# blackfin_a_sdram.net
KiCad netlist of a schematic drawn in Altium Designer
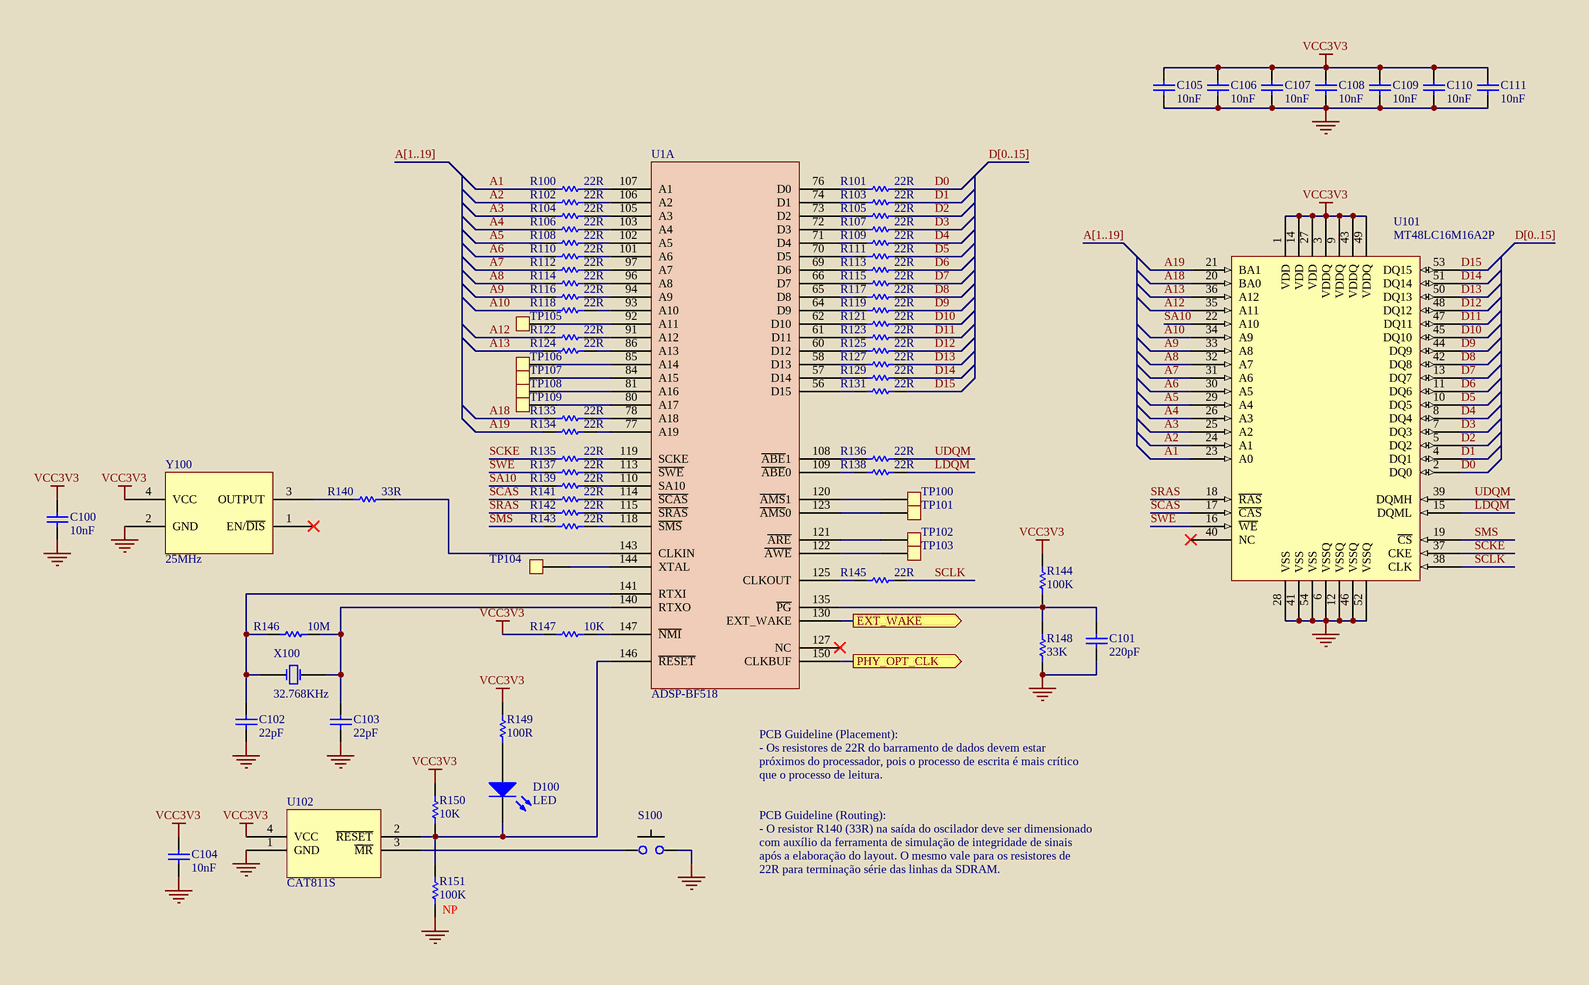
[diagram p0: blackfin_a_sdram.SchDoc]

(export (version "E")
  (design (tool "Eeschema 10.0.6"))
  (components
    (comp (ref "C100")
      (value "10nF")
      (footprint "blackfin_pcblib:C_0603")
      (fields
        (field (name "EVENDORPART#") "77-VJ0603Y103KXAPBC")
        (field (name "MANUFACTURER") "Vishay/Vitramon")
        (field (name "PART#") "VJ0603Y103KXAPW1BC")
      )
      (libsource (lib "blackfin_schlib") (part "Capacitor"))
    )
    (comp (ref "C101")
      (value "220pF")
      (footprint "blackfin_pcblib:C_0603")
      (fields
        (field (name "EVENDORPART#") "81-GRM18R72A221KA01D")
        (field (name "MANUFACTURER") "Murata")
        (field (name "PART#") "GRM188R72A221KA01D")
      )
      (libsource (lib "blackfin_schlib") (part "Capacitor"))
    )
    (comp (ref "C102")
      (value "22pF")
      (footprint "blackfin_pcblib:C_0603")
      (fields
        (field (name "EVENDORPART#") "581-06035A220J")
        (field (name "MANUFACTURER") "AVX")
        (field (name "PART#") "06035A220JAT2A")
      )
      (libsource (lib "blackfin_schlib") (part "Capacitor"))
    )
    (comp (ref "C103")
      (value "22pF")
      (footprint "blackfin_pcblib:C_0603")
      (fields
        (field (name "EVENDORPART#") "581-06035A220J")
        (field (name "MANUFACTURER") "AVX")
        (field (name "PART#") "06035A220JAT2A")
      )
      (libsource (lib "blackfin_schlib") (part "Capacitor"))
    )
    (comp (ref "C104")
      (value "10nF")
      (footprint "blackfin_pcblib:C_0603")
      (fields
        (field (name "EVENDORPART#") "77-VJ0603Y103KXAPBC")
        (field (name "MANUFACTURER") "Vishay/Vitramon")
        (field (name "PART#") "VJ0603Y103KXAPW1BC")
      )
      (libsource (lib "blackfin_schlib") (part "Capacitor"))
    )
    (comp (ref "C105")
      (value "10nF")
      (footprint "blackfin_pcblib:C_0603")
      (fields
        (field (name "EVENDORPART#") "77-VJ0603Y103KXAPBC")
        (field (name "MANUFACTURER") "Vishay/Vitramon")
        (field (name "PART#") "VJ0603Y103KXAPW1BC")
      )
      (libsource (lib "blackfin_schlib") (part "Capacitor"))
    )
    (comp (ref "C106")
      (value "10nF")
      (footprint "blackfin_pcblib:C_0603")
      (fields
        (field (name "EVENDORPART#") "77-VJ0603Y103KXAPBC")
        (field (name "MANUFACTURER") "Vishay/Vitramon")
        (field (name "PART#") "VJ0603Y103KXAPW1BC")
      )
      (libsource (lib "blackfin_schlib") (part "Capacitor"))
    )
    (comp (ref "C107")
      (value "10nF")
      (footprint "blackfin_pcblib:C_0603")
      (fields
        (field (name "EVENDORPART#") "77-VJ0603Y103KXAPBC")
        (field (name "MANUFACTURER") "Vishay/Vitramon")
        (field (name "PART#") "VJ0603Y103KXAPW1BC")
      )
      (libsource (lib "blackfin_schlib") (part "Capacitor"))
    )
    (comp (ref "C108")
      (value "10nF")
      (footprint "blackfin_pcblib:C_0603")
      (fields
        (field (name "EVENDORPART#") "77-VJ0603Y103KXAPBC")
        (field (name "MANUFACTURER") "Vishay/Vitramon")
        (field (name "PART#") "VJ0603Y103KXAPW1BC")
      )
      (libsource (lib "blackfin_schlib") (part "Capacitor"))
    )
    (comp (ref "C109")
      (value "10nF")
      (footprint "blackfin_pcblib:C_0603")
      (fields
        (field (name "EVENDORPART#") "77-VJ0603Y103KXAPBC")
        (field (name "MANUFACTURER") "Vishay/Vitramon")
        (field (name "PART#") "VJ0603Y103KXAPW1BC")
      )
      (libsource (lib "blackfin_schlib") (part "Capacitor"))
    )
    (comp (ref "C110")
      (value "10nF")
      (footprint "blackfin_pcblib:C_0603")
      (fields
        (field (name "EVENDORPART#") "77-VJ0603Y103KXAPBC")
        (field (name "MANUFACTURER") "Vishay/Vitramon")
        (field (name "PART#") "VJ0603Y103KXAPW1BC")
      )
      (libsource (lib "blackfin_schlib") (part "Capacitor"))
    )
    (comp (ref "C111")
      (value "10nF")
      (footprint "blackfin_pcblib:C_0603")
      (fields
        (field (name "EVENDORPART#") "77-VJ0603Y103KXAPBC")
        (field (name "MANUFACTURER") "Vishay/Vitramon")
        (field (name "PART#") "VJ0603Y103KXAPW1BC")
      )
      (libsource (lib "blackfin_schlib") (part "Capacitor"))
    )
    (comp (ref "D100")
      (value "LED")
      (footprint "blackfin_pcblib:LED_0603")
      (description "Red LED")
      (fields (field (name "EVENDORPART#") "638-QTLP600C2TR") (field (name "MANUFACTURER") "Everlight"))
      (libsource (lib "blackfin_schlib") (part "LED"))
    )
    (comp (ref "R100")
      (value "22R")
      (footprint "blackfin_pcblib:R_0402")
      (fields
        (field (name "EVENDORPART#") "71-CRCW0402J-22-E3")
        (field (name "PART#") "CRCW040222R0JNED")
        (field (name "MANUFACTURER") "Vishay/Dale")
      )
      (libsource (lib "blackfin_schlib") (part "Resistor"))
    )
    (comp (ref "R101")
      (value "22R")
      (footprint "blackfin_pcblib:R_0402")
      (fields
        (field (name "EVENDORPART#") "71-CRCW0402J-22-E3")
        (field (name "PART#") "CRCW040222R0JNED")
        (field (name "MANUFACTURER") "Vishay/Dale")
      )
      (libsource (lib "blackfin_schlib") (part "Resistor"))
    )
    (comp (ref "R102")
      (value "22R")
      (footprint "blackfin_pcblib:R_0402")
      (fields
        (field (name "EVENDORPART#") "71-CRCW0402J-22-E3")
        (field (name "PART#") "CRCW040222R0JNED")
        (field (name "MANUFACTURER") "Vishay/Dale")
      )
      (libsource (lib "blackfin_schlib") (part "Resistor"))
    )
    (comp (ref "R103")
      (value "22R")
      (footprint "blackfin_pcblib:R_0402")
      (fields
        (field (name "EVENDORPART#") "71-CRCW0402J-22-E3")
        (field (name "PART#") "CRCW040222R0JNED")
        (field (name "MANUFACTURER") "Vishay/Dale")
      )
      (libsource (lib "blackfin_schlib") (part "Resistor"))
    )
    (comp (ref "R104")
      (value "22R")
      (footprint "blackfin_pcblib:R_0402")
      (fields
        (field (name "EVENDORPART#") "71-CRCW0402J-22-E3")
        (field (name "PART#") "CRCW040222R0JNED")
        (field (name "MANUFACTURER") "Vishay/Dale")
      )
      (libsource (lib "blackfin_schlib") (part "Resistor"))
    )
    (comp (ref "R105")
      (value "22R")
      (footprint "blackfin_pcblib:R_0402")
      (fields
        (field (name "EVENDORPART#") "71-CRCW0402J-22-E3")
        (field (name "PART#") "CRCW040222R0JNED")
        (field (name "MANUFACTURER") "Vishay/Dale")
      )
      (libsource (lib "blackfin_schlib") (part "Resistor"))
    )
    (comp (ref "R106")
      (value "22R")
      (footprint "blackfin_pcblib:R_0402")
      (fields
        (field (name "EVENDORPART#") "71-CRCW0402J-22-E3")
        (field (name "PART#") "CRCW040222R0JNED")
        (field (name "MANUFACTURER") "Vishay/Dale")
      )
      (libsource (lib "blackfin_schlib") (part "Resistor"))
    )
    (comp (ref "R107")
      (value "22R")
      (footprint "blackfin_pcblib:R_0402")
      (fields
        (field (name "EVENDORPART#") "71-CRCW0402J-22-E3")
        (field (name "PART#") "CRCW040222R0JNED")
        (field (name "MANUFACTURER") "Vishay/Dale")
      )
      (libsource (lib "blackfin_schlib") (part "Resistor"))
    )
    (comp (ref "R108")
      (value "22R")
      (footprint "blackfin_pcblib:R_0402")
      (fields
        (field (name "EVENDORPART#") "71-CRCW0402J-22-E3")
        (field (name "PART#") "CRCW040222R0JNED")
        (field (name "MANUFACTURER") "Vishay/Dale")
      )
      (libsource (lib "blackfin_schlib") (part "Resistor"))
    )
    (comp (ref "R109")
      (value "22R")
      (footprint "blackfin_pcblib:R_0402")
      (fields
        (field (name "EVENDORPART#") "71-CRCW0402J-22-E3")
        (field (name "PART#") "CRCW040222R0JNED")
        (field (name "MANUFACTURER") "Vishay/Dale")
      )
      (libsource (lib "blackfin_schlib") (part "Resistor"))
    )
    (comp (ref "R110")
      (value "22R")
      (footprint "blackfin_pcblib:R_0402")
      (fields
        (field (name "EVENDORPART#") "71-CRCW0402J-22-E3")
        (field (name "PART#") "CRCW040222R0JNED")
        (field (name "MANUFACTURER") "Vishay/Dale")
      )
      (libsource (lib "blackfin_schlib") (part "Resistor"))
    )
    (comp (ref "R111")
      (value "22R")
      (footprint "blackfin_pcblib:R_0402")
      (fields
        (field (name "EVENDORPART#") "71-CRCW0402J-22-E3")
        (field (name "PART#") "CRCW040222R0JNED")
        (field (name "MANUFACTURER") "Vishay/Dale")
      )
      (libsource (lib "blackfin_schlib") (part "Resistor"))
    )
    (comp (ref "R112")
      (value "22R")
      (footprint "blackfin_pcblib:R_0402")
      (fields
        (field (name "EVENDORPART#") "71-CRCW0402J-22-E3")
        (field (name "PART#") "CRCW040222R0JNED")
        (field (name "MANUFACTURER") "Vishay/Dale")
      )
      (libsource (lib "blackfin_schlib") (part "Resistor"))
    )
    (comp (ref "R113")
      (value "22R")
      (footprint "blackfin_pcblib:R_0402")
      (fields
        (field (name "EVENDORPART#") "71-CRCW0402J-22-E3")
        (field (name "PART#") "CRCW040222R0JNED")
        (field (name "MANUFACTURER") "Vishay/Dale")
      )
      (libsource (lib "blackfin_schlib") (part "Resistor"))
    )
    (comp (ref "R114")
      (value "22R")
      (footprint "blackfin_pcblib:R_0402")
      (fields
        (field (name "EVENDORPART#") "71-CRCW0402J-22-E3")
        (field (name "PART#") "CRCW040222R0JNED")
        (field (name "MANUFACTURER") "Vishay/Dale")
      )
      (libsource (lib "blackfin_schlib") (part "Resistor"))
    )
    (comp (ref "R115")
      (value "22R")
      (footprint "blackfin_pcblib:R_0402")
      (fields
        (field (name "EVENDORPART#") "71-CRCW0402J-22-E3")
        (field (name "PART#") "CRCW040222R0JNED")
        (field (name "MANUFACTURER") "Vishay/Dale")
      )
      (libsource (lib "blackfin_schlib") (part "Resistor"))
    )
    (comp (ref "R116")
      (value "22R")
      (footprint "blackfin_pcblib:R_0402")
      (fields
        (field (name "EVENDORPART#") "71-CRCW0402J-22-E3")
        (field (name "PART#") "CRCW040222R0JNED")
        (field (name "MANUFACTURER") "Vishay/Dale")
      )
      (libsource (lib "blackfin_schlib") (part "Resistor"))
    )
    (comp (ref "R117")
      (value "22R")
      (footprint "blackfin_pcblib:R_0402")
      (fields
        (field (name "EVENDORPART#") "71-CRCW0402J-22-E3")
        (field (name "PART#") "CRCW040222R0JNED")
        (field (name "MANUFACTURER") "Vishay/Dale")
      )
      (libsource (lib "blackfin_schlib") (part "Resistor"))
    )
    (comp (ref "R118")
      (value "22R")
      (footprint "blackfin_pcblib:R_0402")
      (fields
        (field (name "EVENDORPART#") "71-CRCW0402J-22-E3")
        (field (name "PART#") "CRCW040222R0JNED")
        (field (name "MANUFACTURER") "Vishay/Dale")
      )
      (libsource (lib "blackfin_schlib") (part "Resistor"))
    )
    (comp (ref "R119")
      (value "22R")
      (footprint "blackfin_pcblib:R_0402")
      (fields
        (field (name "EVENDORPART#") "71-CRCW0402J-22-E3")
        (field (name "PART#") "CRCW040222R0JNED")
        (field (name "MANUFACTURER") "Vishay/Dale")
      )
      (libsource (lib "blackfin_schlib") (part "Resistor"))
    )
    (comp (ref "R121")
      (value "22R")
      (footprint "blackfin_pcblib:R_0402")
      (fields
        (field (name "EVENDORPART#") "71-CRCW0402J-22-E3")
        (field (name "PART#") "CRCW040222R0JNED")
        (field (name "MANUFACTURER") "Vishay/Dale")
      )
      (libsource (lib "blackfin_schlib") (part "Resistor"))
    )
    (comp (ref "R122")
      (value "22R")
      (footprint "blackfin_pcblib:R_0402")
      (fields
        (field (name "EVENDORPART#") "71-CRCW0402J-22-E3")
        (field (name "PART#") "CRCW040222R0JNED")
        (field (name "MANUFACTURER") "Vishay/Dale")
      )
      (libsource (lib "blackfin_schlib") (part "Resistor"))
    )
    (comp (ref "R123")
      (value "22R")
      (footprint "blackfin_pcblib:R_0402")
      (fields
        (field (name "EVENDORPART#") "71-CRCW0402J-22-E3")
        (field (name "PART#") "CRCW040222R0JNED")
        (field (name "MANUFACTURER") "Vishay/Dale")
      )
      (libsource (lib "blackfin_schlib") (part "Resistor"))
    )
    (comp (ref "R124")
      (value "22R")
      (footprint "blackfin_pcblib:R_0402")
      (fields
        (field (name "EVENDORPART#") "71-CRCW0402J-22-E3")
        (field (name "PART#") "CRCW040222R0JNED")
        (field (name "MANUFACTURER") "Vishay/Dale")
      )
      (libsource (lib "blackfin_schlib") (part "Resistor"))
    )
    (comp (ref "R125")
      (value "22R")
      (footprint "blackfin_pcblib:R_0402")
      (fields
        (field (name "EVENDORPART#") "71-CRCW0402J-22-E3")
        (field (name "PART#") "CRCW040222R0JNED")
        (field (name "MANUFACTURER") "Vishay/Dale")
      )
      (libsource (lib "blackfin_schlib") (part "Resistor"))
    )
    (comp (ref "R127")
      (value "22R")
      (footprint "blackfin_pcblib:R_0402")
      (fields
        (field (name "EVENDORPART#") "71-CRCW0402J-22-E3")
        (field (name "PART#") "CRCW040222R0JNED")
        (field (name "MANUFACTURER") "Vishay/Dale")
      )
      (libsource (lib "blackfin_schlib") (part "Resistor"))
    )
    (comp (ref "R129")
      (value "22R")
      (footprint "blackfin_pcblib:R_0402")
      (fields
        (field (name "EVENDORPART#") "71-CRCW0402J-22-E3")
        (field (name "PART#") "CRCW040222R0JNED")
        (field (name "MANUFACTURER") "Vishay/Dale")
      )
      (libsource (lib "blackfin_schlib") (part "Resistor"))
    )
    (comp (ref "R131")
      (value "22R")
      (footprint "blackfin_pcblib:R_0402")
      (fields
        (field (name "EVENDORPART#") "71-CRCW0402J-22-E3")
        (field (name "PART#") "CRCW040222R0JNED")
        (field (name "MANUFACTURER") "Vishay/Dale")
      )
      (libsource (lib "blackfin_schlib") (part "Resistor"))
    )
    (comp (ref "R133")
      (value "22R")
      (footprint "blackfin_pcblib:R_0402")
      (fields
        (field (name "EVENDORPART#") "71-CRCW0402J-22-E3")
        (field (name "PART#") "CRCW040222R0JNED")
        (field (name "MANUFACTURER") "Vishay/Dale")
      )
      (libsource (lib "blackfin_schlib") (part "Resistor"))
    )
    (comp (ref "R134")
      (value "22R")
      (footprint "blackfin_pcblib:R_0402")
      (fields
        (field (name "EVENDORPART#") "71-CRCW0402J-22-E3")
        (field (name "PART#") "CRCW040222R0JNED")
        (field (name "MANUFACTURER") "Vishay/Dale")
      )
      (libsource (lib "blackfin_schlib") (part "Resistor"))
    )
    (comp (ref "R135")
      (value "22R")
      (footprint "blackfin_pcblib:R_0402")
      (fields
        (field (name "EVENDORPART#") "71-CRCW0402J-22-E3")
        (field (name "PART#") "CRCW040222R0JNED")
        (field (name "MANUFACTURER") "Vishay/Dale")
      )
      (libsource (lib "blackfin_schlib") (part "Resistor"))
    )
    (comp (ref "R136")
      (value "22R")
      (footprint "blackfin_pcblib:R_0402")
      (fields
        (field (name "EVENDORPART#") "71-CRCW0402J-22-E3")
        (field (name "PART#") "CRCW040222R0JNED")
        (field (name "MANUFACTURER") "Vishay/Dale")
      )
      (libsource (lib "blackfin_schlib") (part "Resistor"))
    )
    (comp (ref "R137")
      (value "22R")
      (footprint "blackfin_pcblib:R_0402")
      (fields
        (field (name "EVENDORPART#") "71-CRCW0402J-22-E3")
        (field (name "PART#") "CRCW040222R0JNED")
        (field (name "MANUFACTURER") "Vishay/Dale")
      )
      (libsource (lib "blackfin_schlib") (part "Resistor"))
    )
    (comp (ref "R138")
      (value "22R")
      (footprint "blackfin_pcblib:R_0402")
      (fields
        (field (name "EVENDORPART#") "71-CRCW0402J-22-E3")
        (field (name "PART#") "CRCW040222R0JNED")
        (field (name "MANUFACTURER") "Vishay/Dale")
      )
      (libsource (lib "blackfin_schlib") (part "Resistor"))
    )
    (comp (ref "R139")
      (value "22R")
      (footprint "blackfin_pcblib:R_0402")
      (fields
        (field (name "EVENDORPART#") "71-CRCW0402J-22-E3")
        (field (name "PART#") "CRCW040222R0JNED")
        (field (name "MANUFACTURER") "Vishay/Dale")
      )
      (libsource (lib "blackfin_schlib") (part "Resistor"))
    )
    (comp (ref "R140")
      (value "33R")
      (footprint "blackfin_pcblib:R_0402")
      (fields
        (field (name "EVENDORPART#") "71-CRCW0402J-33-E3")
        (field (name "PART#") "CRCW040233R0JNED")
        (field (name "MANUFACTURER") "Vishay/Dale")
      )
      (libsource (lib "blackfin_schlib") (part "Resistor"))
    )
    (comp (ref "R141")
      (value "22R")
      (footprint "blackfin_pcblib:R_0402")
      (fields
        (field (name "EVENDORPART#") "71-CRCW0402J-22-E3")
        (field (name "PART#") "CRCW040222R0JNED")
        (field (name "MANUFACTURER") "Vishay/Dale")
      )
      (libsource (lib "blackfin_schlib") (part "Resistor"))
    )
    (comp (ref "R142")
      (value "22R")
      (footprint "blackfin_pcblib:R_0402")
      (fields
        (field (name "EVENDORPART#") "71-CRCW0402J-22-E3")
        (field (name "PART#") "CRCW040222R0JNED")
        (field (name "MANUFACTURER") "Vishay/Dale")
      )
      (libsource (lib "blackfin_schlib") (part "Resistor"))
    )
    (comp (ref "R143")
      (value "22R")
      (footprint "blackfin_pcblib:R_0402")
      (fields
        (field (name "EVENDORPART#") "71-CRCW0402J-22-E3")
        (field (name "PART#") "CRCW040222R0JNED")
        (field (name "MANUFACTURER") "Vishay/Dale")
      )
      (libsource (lib "blackfin_schlib") (part "Resistor"))
    )
    (comp (ref "R144")
      (value "100K")
      (footprint "blackfin_pcblib:R_0603")
      (fields
        (field (name "EVENDORPART#") "71-CRCW0603J-100K-E3")
        (field (name "PART#") "CRCW0603100KJNEA")
        (field (name "MANUFACTURER") "Vishay/Dale")
      )
      (libsource (lib "blackfin_schlib") (part "Resistor"))
    )
    (comp (ref "R145")
      (value "22R")
      (footprint "blackfin_pcblib:R_0402")
      (fields
        (field (name "EVENDORPART#") "71-CRCW0402J-22-E3")
        (field (name "PART#") "CRCW040222R0JNED")
        (field (name "MANUFACTURER") "Vishay/Dale")
      )
      (libsource (lib "blackfin_schlib") (part "Resistor"))
    )
    (comp (ref "R146")
      (value "10M")
      (footprint "blackfin_pcblib:R_0603")
      (fields
        (field (name "EVENDORPART#") "652-CR0603FX-1005ELF")
        (field (name "PART#") "CR0603-FX-1005ELF")
        (field (name "MANUFACTURER") "Bourns")
      )
      (libsource (lib "blackfin_schlib") (part "Resistor"))
    )
    (comp (ref "R147")
      (value "10K")
      (footprint "blackfin_pcblib:R_0603")
      (fields
        (field (name "EVENDORPART#") "71-CRCW0603-10K-E3")
        (field (name "PART#") "CRCW060310K0FKEA")
        (field (name "MANUFACTURER") "Vishay/Dale")
      )
      (libsource (lib "blackfin_schlib") (part "Resistor"))
    )
    (comp (ref "R148")
      (value "33K")
      (footprint "blackfin_pcblib:R_0603")
      (fields
        (field (name "EVENDORPART#") "71-CRCW0603J-33K-E3")
        (field (name "PART#") "CRCW060333K0JNEA")
        (field (name "MANUFACTURER") "Vishay/Dale")
      )
      (libsource (lib "blackfin_schlib") (part "Resistor"))
    )
    (comp (ref "R149")
      (value "100R")
      (footprint "blackfin_pcblib:R_0603")
      (fields
        (field (name "EVENDORPART#") "71-CRCW0603-100-E3")
        (field (name "PART#") "CRCW0603100RFKEA")
        (field (name "MANUFACTURER") "Vishay/Dale")
      )
      (libsource (lib "blackfin_schlib") (part "Resistor"))
    )
    (comp (ref "R150")
      (value "10K")
      (footprint "blackfin_pcblib:R_0603")
      (fields
        (field (name "EVENDORPART#") "71-CRCW0603-10K-E3")
        (field (name "PART#") "CRCW060310K0FKEA")
        (field (name "MANUFACTURER") "Vishay/Dale")
      )
      (libsource (lib "blackfin_schlib") (part "Resistor"))
    )
    (comp (ref "R151")
      (value "100K")
      (footprint "blackfin_pcblib:R_0603")
      (fields
        (field (name "EVENDORPART#") "71-CRCW0603J-100K-E3")
        (field (name "PART#") "CRCW0603100KJNEA")
        (field (name "MANUFACTURER") "Vishay/Dale")
      )
      (libsource (lib "blackfin_schlib") (part "Resistor"))
    )
    (comp (ref "S100")
      (value "Push Button")
      (footprint "blackfin_pcblib:Push Button")
      (fields
        (field (name "EVENDORPART#") "611-PTS645SH50SMTRLF")
        (field (name "PART#") "PTS645SH50SMTRLFS")
        (field (name "MANUFACTURER") "C&K Components")
      )
      (libsource (lib "*") (part "Push Button"))
    )
    (comp (ref "TP100")
      (value "Test Point")
      (footprint "blackfin_pcblib:Test Point")
      (fields (field (name "EVENDORPART#") "NÃO SE APLICA"))
      (libsource (lib "blackfin_schlib") (part "Test Point"))
    )
    (comp (ref "TP101")
      (value "Test Point")
      (footprint "blackfin_pcblib:Test Point")
      (fields (field (name "EVENDORPART#") "NÃO SE APLICA"))
      (libsource (lib "blackfin_schlib") (part "Test Point"))
    )
    (comp (ref "TP102")
      (value "Test Point")
      (footprint "blackfin_pcblib:Test Point")
      (fields (field (name "EVENDORPART#") "NÃO SE APLICA"))
      (libsource (lib "blackfin_schlib") (part "Test Point"))
    )
    (comp (ref "TP103")
      (value "Test Point")
      (footprint "blackfin_pcblib:Test Point")
      (fields (field (name "EVENDORPART#") "NÃO SE APLICA"))
      (libsource (lib "blackfin_schlib") (part "Test Point"))
    )
    (comp (ref "TP104")
      (value "Test Point")
      (footprint "blackfin_pcblib:Test Point")
      (fields (field (name "EVENDORPART#") "NÃO SE APLICA"))
      (libsource (lib "") (part "Test Point_1"))
    )
    (comp (ref "TP105")
      (value "Test Point")
      (footprint "blackfin_pcblib:Test Point")
      (fields (field (name "EVENDORPART#") "NÃO SE APLICA"))
      (libsource (lib "") (part "Test Point_1"))
    )
    (comp (ref "TP106")
      (value "Test Point")
      (footprint "blackfin_pcblib:Test Point")
      (fields (field (name "EVENDORPART#") "NÃO SE APLICA"))
      (libsource (lib "") (part "Test Point_1"))
    )
    (comp (ref "TP107")
      (value "Test Point")
      (footprint "blackfin_pcblib:Test Point")
      (fields (field (name "EVENDORPART#") "NÃO SE APLICA"))
      (libsource (lib "") (part "Test Point_1"))
    )
    (comp (ref "TP108")
      (value "Test Point")
      (footprint "blackfin_pcblib:Test Point")
      (fields (field (name "EVENDORPART#") "NÃO SE APLICA"))
      (libsource (lib "") (part "Test Point_1"))
    )
    (comp (ref "TP109")
      (value "Test Point")
      (footprint "blackfin_pcblib:Test Point")
      (fields (field (name "EVENDORPART#") "NÃO SE APLICA"))
      (libsource (lib "") (part "Test Point_1"))
    )
    (comp (ref "U1")
      (value "ADSP-BF518")
      (footprint "blackfin_pcblib:LQFP-176")
      (fields (field (name "EVENDORPART#") "ADSP-BF518BSWZ-4") (field (name "MANUFACTURER") "Analog Devices"))
      (libsource (lib "blackfin_schlib") (part "ADSP-BF518"))
    )
    (comp (ref "U101")
      (value "MT48LC16M16A2P")
      (footprint "blackfin_pcblib:TSOP-54")
      (fields
        (field (name "PART#") "MT48LC16M16A2P-75:D TR")
        (field (name "EVENDORPART#") "557-1059-1-ND")
        (field (name "MANUFACTURER") "Micron")
      )
      (libsource (lib "blackfin_schlib") (part "MT48LC16M16A2P"))
    )
    (comp (ref "U102")
      (value "CAT811S")
      (footprint "blackfin_pcblib:SOT-143")
      (fields
        (field (name "PART#") "CAT811STBI-GT3")
        (field (name "MANUFACTURER") "ON Semiconductor")
        (field (name "EVENDORPART#") "698-CAT811STBI-GT3")
      )
      (libsource (lib "*") (part "CAT811S"))
    )
    (comp (ref "X100")
      (value "32.768KHz")
      (footprint "blackfin_pcblib:XTAL_32.768kHz")
      (fields
        (field (name "EVENDORPART#") "SER2405CT-ND")
        (field (name "PART#") "MC-405")
        (field (name "MANUFACTURER") "Epson")
      )
      (libsource (lib "blackfin_schlib") (part "XTAL"))
    )
    (comp (ref "Y100")
      (value "25MHz")
      (footprint "blackfin_pcblib:OSC_25MHz")
      (fields
        (field (name "EVENDORPART#") "815-ASV-25-EJ-T")
        (field (name "PART#") "ASV-25.000MHZ-EJ-T")
        (field (name "MANUFACTURER") "ABRACON")
      )
      (libsource (lib "blackfin_schlib") (part "Oscillator_25MHz"))
    )
  )
  (nets
    (net (code "6") (name "/A1") (class "Default")
      (node (ref "R100") (pin "1") (pinfunction "1_1") (pintype "passive"))
      (node (ref "U101") (pin "23") (pinfunction "A0_23") (pintype "input"))
    )
    (net (code "7") (name "/A2") (class "Default")
      (node (ref "R102") (pin "1") (pinfunction "1_1") (pintype "passive"))
      (node (ref "U101") (pin "24") (pinfunction "A1_24") (pintype "input"))
    )
    (net (code "8") (name "/A3") (class "Default")
      (node (ref "R104") (pin "1") (pinfunction "1_1") (pintype "passive"))
      (node (ref "U101") (pin "25") (pinfunction "A2_25") (pintype "input"))
    )
    (net (code "9") (name "/A4") (class "Default")
      (node (ref "R106") (pin "1") (pinfunction "1_1") (pintype "passive"))
      (node (ref "U101") (pin "26") (pinfunction "A3_26") (pintype "input"))
    )
    (net (code "10") (name "/A5") (class "Default")
      (node (ref "R108") (pin "1") (pinfunction "1_1") (pintype "passive"))
      (node (ref "U101") (pin "29") (pinfunction "A4_29") (pintype "input"))
    )
    (net (code "11") (name "/A6") (class "Default")
      (node (ref "R110") (pin "1") (pinfunction "1_1") (pintype "passive"))
      (node (ref "U101") (pin "30") (pinfunction "A5_30") (pintype "input"))
    )
    (net (code "12") (name "/A7") (class "Default")
      (node (ref "R112") (pin "1") (pinfunction "1_1") (pintype "passive"))
      (node (ref "U101") (pin "31") (pinfunction "A6_31") (pintype "input"))
    )
    (net (code "13") (name "/A8") (class "Default")
      (node (ref "R114") (pin "1") (pinfunction "1_1") (pintype "passive"))
      (node (ref "U101") (pin "32") (pinfunction "A7_32") (pintype "input"))
    )
    (net (code "14") (name "/A9") (class "Default")
      (node (ref "R116") (pin "1") (pinfunction "1_1") (pintype "passive"))
      (node (ref "U101") (pin "33") (pinfunction "A8_33") (pintype "input"))
    )
    (net (code "15") (name "/A10") (class "Default")
      (node (ref "R118") (pin "1") (pinfunction "1_1") (pintype "passive"))
      (node (ref "U101") (pin "34") (pinfunction "A9_34") (pintype "input"))
    )
    (net (code "16") (name "/A12") (class "Default")
      (node (ref "R122") (pin "1") (pinfunction "1_1") (pintype "passive"))
      (node (ref "U101") (pin "35") (pinfunction "A11_35") (pintype "input"))
    )
    (net (code "17") (name "/A13") (class "Default")
      (node (ref "R124") (pin "1") (pinfunction "1_1") (pintype "passive"))
      (node (ref "U101") (pin "36") (pinfunction "A12_36") (pintype "input"))
    )
    (net (code "18") (name "/A18") (class "Default")
      (node (ref "R133") (pin "1") (pinfunction "1_1") (pintype "passive"))
      (node (ref "U101") (pin "20") (pinfunction "BA0_20") (pintype "input"))
    )
    (net (code "19") (name "/A19") (class "Default")
      (node (ref "R134") (pin "1") (pinfunction "1_1") (pintype "passive"))
      (node (ref "U101") (pin "21") (pinfunction "BA1_21") (pintype "input"))
    )
    (net (code "21") (name "/D0") (class "Default")
      (node (ref "R101") (pin "2") (pinfunction "2_2") (pintype "passive"))
      (node (ref "U101") (pin "2") (pinfunction "DQ0_2") (pintype "bidirectional"))
    )
    (net (code "22") (name "/D1") (class "Default")
      (node (ref "R103") (pin "2") (pinfunction "2_2") (pintype "passive"))
      (node (ref "U101") (pin "4") (pinfunction "DQ1_4") (pintype "bidirectional"))
    )
    (net (code "23") (name "/D2") (class "Default")
      (node (ref "R105") (pin "2") (pinfunction "2_2") (pintype "passive"))
      (node (ref "U101") (pin "5") (pinfunction "DQ2_5") (pintype "bidirectional"))
    )
    (net (code "24") (name "/D3") (class "Default")
      (node (ref "R107") (pin "2") (pinfunction "2_2") (pintype "passive"))
      (node (ref "U101") (pin "7") (pinfunction "DQ3_7") (pintype "bidirectional"))
    )
    (net (code "25") (name "/D4") (class "Default")
      (node (ref "R109") (pin "2") (pinfunction "2_2") (pintype "passive"))
      (node (ref "U101") (pin "8") (pinfunction "DQ4_8") (pintype "bidirectional"))
    )
    (net (code "26") (name "/D5") (class "Default")
      (node (ref "R111") (pin "2") (pinfunction "2_2") (pintype "passive"))
      (node (ref "U101") (pin "10") (pinfunction "DQ5_10") (pintype "bidirectional"))
    )
    (net (code "27") (name "/D6") (class "Default")
      (node (ref "R113") (pin "2") (pinfunction "2_2") (pintype "passive"))
      (node (ref "U101") (pin "11") (pinfunction "DQ6_11") (pintype "bidirectional"))
    )
    (net (code "28") (name "/D7") (class "Default")
      (node (ref "R115") (pin "2") (pinfunction "2_2") (pintype "passive"))
      (node (ref "U101") (pin "13") (pinfunction "DQ7_13") (pintype "bidirectional"))
    )
    (net (code "29") (name "/D8") (class "Default")
      (node (ref "R117") (pin "2") (pinfunction "2_2") (pintype "passive"))
      (node (ref "U101") (pin "42") (pinfunction "DQ8_42") (pintype "bidirectional"))
    )
    (net (code "30") (name "/D9") (class "Default")
      (node (ref "R119") (pin "2") (pinfunction "2_2") (pintype "passive"))
      (node (ref "U101") (pin "44") (pinfunction "DQ9_44") (pintype "bidirectional"))
    )
    (net (code "31") (name "/D10") (class "Default")
      (node (ref "R121") (pin "2") (pinfunction "2_2") (pintype "passive"))
      (node (ref "U101") (pin "45") (pinfunction "DQ10_45") (pintype "bidirectional"))
    )
    (net (code "32") (name "/D11") (class "Default")
      (node (ref "R123") (pin "2") (pinfunction "2_2") (pintype "passive"))
      (node (ref "U101") (pin "47") (pinfunction "DQ11_47") (pintype "bidirectional"))
    )
    (net (code "33") (name "/D12") (class "Default")
      (node (ref "R125") (pin "2") (pinfunction "2_2") (pintype "passive"))
      (node (ref "U101") (pin "48") (pinfunction "DQ12_48") (pintype "bidirectional"))
    )
    (net (code "34") (name "/D13") (class "Default")
      (node (ref "R127") (pin "2") (pinfunction "2_2") (pintype "passive"))
      (node (ref "U101") (pin "50") (pinfunction "DQ13_50") (pintype "bidirectional"))
    )
    (net (code "35") (name "/D14") (class "Default")
      (node (ref "R129") (pin "2") (pinfunction "2_2") (pintype "passive"))
      (node (ref "U101") (pin "51") (pinfunction "DQ14_51") (pintype "bidirectional"))
    )
    (net (code "36") (name "/D15") (class "Default")
      (node (ref "R131") (pin "2") (pinfunction "2_2") (pintype "passive"))
      (node (ref "U101") (pin "53") (pinfunction "DQ15_53") (pintype "bidirectional"))
    )
    (net (code "38") (name "/EXT_WAKE") (class "Default")
      (node (ref "U1") (pin "130") (pinfunction "EXT_WAKE_130") (pintype "passive"))
    )
    (net (code "39") (name "/LDQM") (class "Default")
      (node (ref "R138") (pin "2") (pinfunction "2_2") (pintype "passive"))
      (node (ref "U101") (pin "15") (pinfunction "DQML_15") (pintype "input"))
    )
    (net (code "40") (name "/PHY_OPT_CLK") (class "Default")
      (node (ref "U1") (pin "150") (pinfunction "CLKBUF_150") (pintype "passive"))
    )
    (net (code "41") (name "/SA10") (class "Default")
      (node (ref "R139") (pin "1") (pinfunction "1_1") (pintype "passive"))
      (node (ref "U101") (pin "22") (pinfunction "A10_22") (pintype "input"))
    )
    (net (code "42") (name "/SCAS") (class "Default")
      (node (ref "R141") (pin "1") (pinfunction "1_1") (pintype "passive"))
      (node (ref "U101") (pin "17") (pinfunction "~{CAS}_17") (pintype "input"))
    )
    (net (code "43") (name "/SCKE") (class "Default")
      (node (ref "R135") (pin "1") (pinfunction "1_1") (pintype "passive"))
      (node (ref "U101") (pin "37") (pinfunction "CKE_37") (pintype "input"))
    )
    (net (code "44") (name "/SCLK") (class "Default")
      (node (ref "R145") (pin "2") (pinfunction "2_2") (pintype "passive"))
      (node (ref "U101") (pin "38") (pinfunction "CLK_38") (pintype "input"))
    )
    (net (code "45") (name "/SMS") (class "Default")
      (node (ref "R143") (pin "1") (pinfunction "1_1") (pintype "passive"))
      (node (ref "U101") (pin "19") (pinfunction "~{CS}_19") (pintype "input"))
    )
    (net (code "46") (name "/SRAS") (class "Default")
      (node (ref "R142") (pin "1") (pinfunction "1_1") (pintype "passive"))
      (node (ref "U101") (pin "18") (pinfunction "~{RAS}_18") (pintype "input"))
    )
    (net (code "47") (name "/SWE") (class "Default")
      (node (ref "R137") (pin "1") (pinfunction "1_1") (pintype "passive"))
      (node (ref "U101") (pin "16") (pinfunction "~{WE}_16") (pintype "input"))
    )
    (net (code "48") (name "/UDQM") (class "Default")
      (node (ref "R136") (pin "2") (pinfunction "2_2") (pintype "passive"))
      (node (ref "U101") (pin "39") (pinfunction "DQMH_39") (pintype "input"))
    )
    (net (code "49") (name "GND") (class "Default")
      (node (ref "C100") (pin "1") (pinfunction "1_1") (pintype "passive"))
      (node (ref "C101") (pin "1") (pinfunction "1_1") (pintype "passive"))
      (node (ref "C102") (pin "1") (pinfunction "1_1") (pintype "passive"))
      (node (ref "C103") (pin "1") (pinfunction "1_1") (pintype "passive"))
      (node (ref "C104") (pin "1") (pinfunction "1_1") (pintype "passive"))
      (node (ref "C105") (pin "1") (pinfunction "1_1") (pintype "passive"))
      (node (ref "C106") (pin "1") (pinfunction "1_1") (pintype "passive"))
      (node (ref "C107") (pin "1") (pinfunction "1_1") (pintype "passive"))
      (node (ref "C108") (pin "1") (pinfunction "1_1") (pintype "passive"))
      (node (ref "C109") (pin "1") (pinfunction "1_1") (pintype "passive"))
      (node (ref "C110") (pin "1") (pinfunction "1_1") (pintype "passive"))
      (node (ref "C111") (pin "1") (pinfunction "1_1") (pintype "passive"))
      (node (ref "R148") (pin "1") (pinfunction "1_1") (pintype "passive"))
      (node (ref "R151") (pin "1") (pinfunction "1_1") (pintype "passive"))
      (node (ref "S100") (pin "2") (pinfunction "2_2") (pintype "passive"))
      (node (ref "U101") (pin "12") (pinfunction "VSSQ_12") (pintype "power_in"))
      (node (ref "U101") (pin "28") (pinfunction "VSS_28") (pintype "power_in"))
      (node (ref "U101") (pin "41") (pinfunction "VSS_41") (pintype "power_in"))
      (node (ref "U101") (pin "46") (pinfunction "VSSQ_46") (pintype "power_in"))
      (node (ref "U101") (pin "52") (pinfunction "VSSQ_52") (pintype "power_in"))
      (node (ref "U101") (pin "54") (pinfunction "VSS_54") (pintype "power_in"))
      (node (ref "U101") (pin "6") (pinfunction "VSSQ_6") (pintype "power_in"))
      (node (ref "U102") (pin "1") (pinfunction "GND_1") (pintype "passive"))
      (node (ref "Y100") (pin "2") (pinfunction "GND_2") (pintype "passive"))
    )
    (net (code "50") (name "Net-(D100-A)") (class "Default")
      (node (ref "D100") (pin "1") (pinfunction "A_1") (pintype "passive"))
      (node (ref "R149") (pin "1") (pinfunction "1_1") (pintype "passive"))
    )
    (net (code "51") (name "Net-(D100-K)") (class "Default")
      (node (ref "D100") (pin "2") (pinfunction "K_2") (pintype "passive"))
      (node (ref "R150") (pin "2") (pinfunction "2_2") (pintype "passive"))
      (node (ref "R151") (pin "2") (pinfunction "2_2") (pintype "passive"))
      (node (ref "U1") (pin "146") (pinfunction "~{RESET}_146") (pintype "passive"))
      (node (ref "U102") (pin "2") (pinfunction "~{RESET}_2") (pintype "passive"))
    )
    (net (code "52") (name "Net-(U1A-A1)") (class "Default")
      (node (ref "R100") (pin "2") (pinfunction "2_2") (pintype "passive"))
      (node (ref "U1") (pin "107") (pinfunction "A1_107") (pintype "passive"))
    )
    (net (code "53") (name "Net-(U1A-A2)") (class "Default")
      (node (ref "R102") (pin "2") (pinfunction "2_2") (pintype "passive"))
      (node (ref "U1") (pin "106") (pinfunction "A2_106") (pintype "passive"))
    )
    (net (code "54") (name "Net-(U1A-A3)") (class "Default")
      (node (ref "R104") (pin "2") (pinfunction "2_2") (pintype "passive"))
      (node (ref "U1") (pin "105") (pinfunction "A3_105") (pintype "passive"))
    )
    (net (code "55") (name "Net-(U1A-A4)") (class "Default")
      (node (ref "R106") (pin "2") (pinfunction "2_2") (pintype "passive"))
      (node (ref "U1") (pin "103") (pinfunction "A4_103") (pintype "passive"))
    )
    (net (code "56") (name "Net-(U1A-A5)") (class "Default")
      (node (ref "R108") (pin "2") (pinfunction "2_2") (pintype "passive"))
      (node (ref "U1") (pin "102") (pinfunction "A5_102") (pintype "passive"))
    )
    (net (code "57") (name "Net-(U1A-A6)") (class "Default")
      (node (ref "R110") (pin "2") (pinfunction "2_2") (pintype "passive"))
      (node (ref "U1") (pin "101") (pinfunction "A6_101") (pintype "passive"))
    )
    (net (code "58") (name "Net-(U1A-A7)") (class "Default")
      (node (ref "R112") (pin "2") (pinfunction "2_2") (pintype "passive"))
      (node (ref "U1") (pin "97") (pinfunction "A7_97") (pintype "passive"))
    )
    (net (code "59") (name "Net-(U1A-A8)") (class "Default")
      (node (ref "R114") (pin "2") (pinfunction "2_2") (pintype "passive"))
      (node (ref "U1") (pin "96") (pinfunction "A8_96") (pintype "passive"))
    )
    (net (code "60") (name "Net-(U1A-A9)") (class "Default")
      (node (ref "R116") (pin "2") (pinfunction "2_2") (pintype "passive"))
      (node (ref "U1") (pin "94") (pinfunction "A9_94") (pintype "passive"))
    )
    (net (code "61") (name "Net-(U1A-A10)") (class "Default")
      (node (ref "R118") (pin "2") (pinfunction "2_2") (pintype "passive"))
      (node (ref "U1") (pin "93") (pinfunction "A10_93") (pintype "passive"))
    )
    (net (code "62") (name "Net-(U1A-A11)") (class "Default")
      (node (ref "TP105") (pin "1") (pinfunction "1_1") (pintype "passive"))
      (node (ref "U1") (pin "92") (pinfunction "A11_92") (pintype "passive"))
    )
    (net (code "63") (name "Net-(U1A-A12)") (class "Default")
      (node (ref "R122") (pin "2") (pinfunction "2_2") (pintype "passive"))
      (node (ref "U1") (pin "91") (pinfunction "A12_91") (pintype "passive"))
    )
    (net (code "64") (name "Net-(U1A-A13)") (class "Default")
      (node (ref "R124") (pin "2") (pinfunction "2_2") (pintype "passive"))
      (node (ref "U1") (pin "86") (pinfunction "A13_86") (pintype "passive"))
    )
    (net (code "65") (name "Net-(U1A-A14)") (class "Default")
      (node (ref "TP106") (pin "1") (pinfunction "1_1") (pintype "passive"))
      (node (ref "U1") (pin "85") (pinfunction "A14_85") (pintype "passive"))
    )
    (net (code "66") (name "Net-(U1A-A15)") (class "Default")
      (node (ref "TP107") (pin "1") (pinfunction "1_1") (pintype "passive"))
      (node (ref "U1") (pin "84") (pinfunction "A15_84") (pintype "passive"))
    )
    (net (code "67") (name "Net-(U1A-A16)") (class "Default")
      (node (ref "TP108") (pin "1") (pinfunction "1_1") (pintype "passive"))
      (node (ref "U1") (pin "81") (pinfunction "A16_81") (pintype "passive"))
    )
    (net (code "68") (name "Net-(U1A-A17)") (class "Default")
      (node (ref "TP109") (pin "1") (pinfunction "1_1") (pintype "passive"))
      (node (ref "U1") (pin "80") (pinfunction "A17_80") (pintype "passive"))
    )
    (net (code "69") (name "Net-(U1A-A18)") (class "Default")
      (node (ref "R133") (pin "2") (pinfunction "2_2") (pintype "passive"))
      (node (ref "U1") (pin "78") (pinfunction "A18_78") (pintype "passive"))
    )
    (net (code "70") (name "Net-(U1A-A19)") (class "Default")
      (node (ref "R134") (pin "2") (pinfunction "2_2") (pintype "passive"))
      (node (ref "U1") (pin "77") (pinfunction "A19_77") (pintype "passive"))
    )
    (net (code "71") (name "Net-(U1A-CLKIN)") (class "Default")
      (node (ref "R140") (pin "2") (pinfunction "2_2") (pintype "passive"))
      (node (ref "U1") (pin "143") (pinfunction "CLKIN_143") (pintype "passive"))
    )
    (net (code "72") (name "Net-(U1A-CLKOUT)") (class "Default")
      (node (ref "R145") (pin "1") (pinfunction "1_1") (pintype "passive"))
      (node (ref "U1") (pin "125") (pinfunction "CLKOUT_125") (pintype "passive"))
    )
    (net (code "73") (name "Net-(U1A-D0)") (class "Default")
      (node (ref "R101") (pin "1") (pinfunction "1_1") (pintype "passive"))
      (node (ref "U1") (pin "76") (pinfunction "D0_76") (pintype "passive"))
    )
    (net (code "74") (name "Net-(U1A-D1)") (class "Default")
      (node (ref "R103") (pin "1") (pinfunction "1_1") (pintype "passive"))
      (node (ref "U1") (pin "74") (pinfunction "D1_74") (pintype "passive"))
    )
    (net (code "75") (name "Net-(U1A-D2)") (class "Default")
      (node (ref "R105") (pin "1") (pinfunction "1_1") (pintype "passive"))
      (node (ref "U1") (pin "73") (pinfunction "D2_73") (pintype "passive"))
    )
    (net (code "76") (name "Net-(U1A-D3)") (class "Default")
      (node (ref "R107") (pin "1") (pinfunction "1_1") (pintype "passive"))
      (node (ref "U1") (pin "72") (pinfunction "D3_72") (pintype "passive"))
    )
    (net (code "77") (name "Net-(U1A-D4)") (class "Default")
      (node (ref "R109") (pin "1") (pinfunction "1_1") (pintype "passive"))
      (node (ref "U1") (pin "71") (pinfunction "D4_71") (pintype "passive"))
    )
    (net (code "78") (name "Net-(U1A-D5)") (class "Default")
      (node (ref "R111") (pin "1") (pinfunction "1_1") (pintype "passive"))
      (node (ref "U1") (pin "70") (pinfunction "D5_70") (pintype "passive"))
    )
    (net (code "79") (name "Net-(U1A-D6)") (class "Default")
      (node (ref "R113") (pin "1") (pinfunction "1_1") (pintype "passive"))
      (node (ref "U1") (pin "69") (pinfunction "D6_69") (pintype "passive"))
    )
    (net (code "80") (name "Net-(U1A-D7)") (class "Default")
      (node (ref "R115") (pin "1") (pinfunction "1_1") (pintype "passive"))
      (node (ref "U1") (pin "66") (pinfunction "D7_66") (pintype "passive"))
    )
    (net (code "81") (name "Net-(U1A-D8)") (class "Default")
      (node (ref "R117") (pin "1") (pinfunction "1_1") (pintype "passive"))
      (node (ref "U1") (pin "65") (pinfunction "D8_65") (pintype "passive"))
    )
    (net (code "82") (name "Net-(U1A-D9)") (class "Default")
      (node (ref "R119") (pin "1") (pinfunction "1_1") (pintype "passive"))
      (node (ref "U1") (pin "64") (pinfunction "D9_64") (pintype "passive"))
    )
    (net (code "83") (name "Net-(U1A-D10)") (class "Default")
      (node (ref "R121") (pin "1") (pinfunction "1_1") (pintype "passive"))
      (node (ref "U1") (pin "62") (pinfunction "D10_62") (pintype "passive"))
    )
    (net (code "84") (name "Net-(U1A-D11)") (class "Default")
      (node (ref "R123") (pin "1") (pinfunction "1_1") (pintype "passive"))
      (node (ref "U1") (pin "61") (pinfunction "D11_61") (pintype "passive"))
    )
    (net (code "85") (name "Net-(U1A-D12)") (class "Default")
      (node (ref "R125") (pin "1") (pinfunction "1_1") (pintype "passive"))
      (node (ref "U1") (pin "60") (pinfunction "D12_60") (pintype "passive"))
    )
    (net (code "86") (name "Net-(U1A-D13)") (class "Default")
      (node (ref "R127") (pin "1") (pinfunction "1_1") (pintype "passive"))
      (node (ref "U1") (pin "58") (pinfunction "D13_58") (pintype "passive"))
    )
    (net (code "87") (name "Net-(U1A-D14)") (class "Default")
      (node (ref "R129") (pin "1") (pinfunction "1_1") (pintype "passive"))
      (node (ref "U1") (pin "57") (pinfunction "D14_57") (pintype "passive"))
    )
    (net (code "88") (name "Net-(U1A-D15)") (class "Default")
      (node (ref "R131") (pin "1") (pinfunction "1_1") (pintype "passive"))
      (node (ref "U1") (pin "56") (pinfunction "D15_56") (pintype "passive"))
    )
    (net (code "89") (name "Net-(U1A-RTXI)") (class "Default")
      (node (ref "C102") (pin "2") (pinfunction "2_2") (pintype "passive"))
      (node (ref "R146") (pin "1") (pinfunction "1_1") (pintype "passive"))
      (node (ref "U1") (pin "141") (pinfunction "RTXI_141") (pintype "passive"))
      (node (ref "X100") (pin "1") (pinfunction "OSC1_1") (pintype "passive"))
    )
    (net (code "90") (name "Net-(U1A-RTXO)") (class "Default")
      (node (ref "C103") (pin "2") (pinfunction "2_2") (pintype "passive"))
      (node (ref "R146") (pin "2") (pinfunction "2_2") (pintype "passive"))
      (node (ref "U1") (pin "140") (pinfunction "RTXO_140") (pintype "passive"))
      (node (ref "X100") (pin "2") (pinfunction "OSC2_2") (pintype "passive"))
    )
    (net (code "91") (name "Net-(U1A-SA10)") (class "Default")
      (node (ref "R139") (pin "2") (pinfunction "2_2") (pintype "passive"))
      (node (ref "U1") (pin "110") (pinfunction "SA10_110") (pintype "passive"))
    )
    (net (code "92") (name "Net-(U1A-SCKE)") (class "Default")
      (node (ref "R135") (pin "2") (pinfunction "2_2") (pintype "passive"))
      (node (ref "U1") (pin "119") (pinfunction "SCKE_119") (pintype "passive"))
    )
    (net (code "93") (name "Net-(U1A-XTAL)") (class "Default")
      (node (ref "TP104") (pin "1") (pinfunction "1_1") (pintype "passive"))
      (node (ref "U1") (pin "144") (pinfunction "XTAL_144") (pintype "passive"))
    )
    (net (code "94") (name "Net-(U1A-~{ABE}0)") (class "Default")
      (node (ref "R138") (pin "1") (pinfunction "1_1") (pintype "passive"))
      (node (ref "U1") (pin "109") (pinfunction "~{ABE}0_109") (pintype "passive"))
    )
    (net (code "95") (name "Net-(U1A-~{ABE}1)") (class "Default")
      (node (ref "R136") (pin "1") (pinfunction "1_1") (pintype "passive"))
      (node (ref "U1") (pin "108") (pinfunction "~{ABE}1_108") (pintype "passive"))
    )
    (net (code "96") (name "Net-(U1A-~{AMS}0)") (class "Default")
      (node (ref "TP101") (pin "1") (pinfunction "1_1") (pintype "passive"))
      (node (ref "U1") (pin "123") (pinfunction "~{AMS}0_123") (pintype "passive"))
    )
    (net (code "97") (name "Net-(U1A-~{AMS}1)") (class "Default")
      (node (ref "TP100") (pin "1") (pinfunction "1_1") (pintype "passive"))
      (node (ref "U1") (pin "120") (pinfunction "~{AMS}1_120") (pintype "passive"))
    )
    (net (code "98") (name "Net-(U1A-~{ARE})") (class "Default")
      (node (ref "TP102") (pin "1") (pinfunction "1_1") (pintype "passive"))
      (node (ref "U1") (pin "121") (pinfunction "~{ARE}_121") (pintype "passive"))
    )
    (net (code "99") (name "Net-(U1A-~{AWE})") (class "Default")
      (node (ref "TP103") (pin "1") (pinfunction "1_1") (pintype "passive"))
      (node (ref "U1") (pin "122") (pinfunction "~{AWE}_122") (pintype "passive"))
    )
    (net (code "100") (name "Net-(U1A-~{NMI})") (class "Default")
      (node (ref "R147") (pin "1") (pinfunction "1_1") (pintype "passive"))
      (node (ref "U1") (pin "147") (pinfunction "~{NMI}_147") (pintype "passive"))
    )
    (net (code "101") (name "Net-(U1A-~{PG})") (class "Default")
      (node (ref "C101") (pin "2") (pinfunction "2_2") (pintype "passive"))
      (node (ref "R144") (pin "1") (pinfunction "1_1") (pintype "passive"))
      (node (ref "R148") (pin "2") (pinfunction "2_2") (pintype "passive"))
      (node (ref "U1") (pin "135") (pinfunction "~{PG}_135") (pintype "passive"))
    )
    (net (code "102") (name "Net-(U1A-~{SCAS})") (class "Default")
      (node (ref "R141") (pin "2") (pinfunction "2_2") (pintype "passive"))
      (node (ref "U1") (pin "114") (pinfunction "~{SCAS}_114") (pintype "passive"))
    )
    (net (code "103") (name "Net-(U1A-~{SMS})") (class "Default")
      (node (ref "R143") (pin "2") (pinfunction "2_2") (pintype "passive"))
      (node (ref "U1") (pin "118") (pinfunction "~{SMS}_118") (pintype "passive"))
    )
    (net (code "104") (name "Net-(U1A-~{SRAS})") (class "Default")
      (node (ref "R142") (pin "2") (pinfunction "2_2") (pintype "passive"))
      (node (ref "U1") (pin "115") (pinfunction "~{SRAS}_115") (pintype "passive"))
    )
    (net (code "105") (name "Net-(U1A-~{SWE})") (class "Default")
      (node (ref "R137") (pin "2") (pinfunction "2_2") (pintype "passive"))
      (node (ref "U1") (pin "113") (pinfunction "~{SWE}_113") (pintype "passive"))
    )
    (net (code "106") (name "Net-(U102-~{MR})") (class "Default")
      (node (ref "S100") (pin "1") (pinfunction "1_1") (pintype "passive"))
      (node (ref "U102") (pin "3") (pinfunction "~{MR}_3") (pintype "passive"))
    )
    (net (code "107") (name "Net-(Y100-OUTPUT)") (class "Default")
      (node (ref "R140") (pin "1") (pinfunction "1_1") (pintype "passive"))
      (node (ref "Y100") (pin "3") (pinfunction "OUTPUT_3") (pintype "passive"))
    )
    (net (code "108") (name "VCC3V3") (class "Default")
      (node (ref "C100") (pin "2") (pinfunction "2_2") (pintype "passive"))
      (node (ref "C104") (pin "2") (pinfunction "2_2") (pintype "passive"))
      (node (ref "C105") (pin "2") (pinfunction "2_2") (pintype "passive"))
      (node (ref "C106") (pin "2") (pinfunction "2_2") (pintype "passive"))
      (node (ref "C107") (pin "2") (pinfunction "2_2") (pintype "passive"))
      (node (ref "C108") (pin "2") (pinfunction "2_2") (pintype "passive"))
      (node (ref "C109") (pin "2") (pinfunction "2_2") (pintype "passive"))
      (node (ref "C110") (pin "2") (pinfunction "2_2") (pintype "passive"))
      (node (ref "C111") (pin "2") (pinfunction "2_2") (pintype "passive"))
      (node (ref "R144") (pin "2") (pinfunction "2_2") (pintype "passive"))
      (node (ref "R147") (pin "2") (pinfunction "2_2") (pintype "passive"))
      (node (ref "R149") (pin "2") (pinfunction "2_2") (pintype "passive"))
      (node (ref "R150") (pin "1") (pinfunction "1_1") (pintype "passive"))
      (node (ref "U101") (pin "1") (pinfunction "VDD_1") (pintype "power_in"))
      (node (ref "U101") (pin "14") (pinfunction "VDD_14") (pintype "power_in"))
      (node (ref "U101") (pin "27") (pinfunction "VDD_27") (pintype "power_in"))
      (node (ref "U101") (pin "3") (pinfunction "VDDQ_3") (pintype "power_in"))
      (node (ref "U101") (pin "43") (pinfunction "VDDQ_43") (pintype "power_in"))
      (node (ref "U101") (pin "49") (pinfunction "VDDQ_49") (pintype "power_in"))
      (node (ref "U101") (pin "9") (pinfunction "VDDQ_9") (pintype "power_in"))
      (node (ref "U102") (pin "4") (pinfunction "VCC_4") (pintype "passive"))
      (node (ref "Y100") (pin "4") (pinfunction "VCC_4") (pintype "passive"))
    )
    (net (code "109") (name "unconnected-(U1A-NC-Pad127)") (class "Default")
      (node (ref "U1") (pin "127") (pinfunction "NC_127") (pintype "passive+no_connect"))
    )
    (net (code "110") (name "unconnected-(U101-NC-Pad40)") (class "Default")
      (node (ref "U101") (pin "40") (pinfunction "NC_40") (pintype "passive+no_connect"))
    )
    (net (code "111") (name "unconnected-(Y100-EN{slash}~{DIS}-Pad1)") (class "Default")
      (node (ref "Y100") (pin "1") (pinfunction "EN/~{DIS}_1") (pintype "passive+no_connect"))
    )
  )
)
